# LB_BIT_w9_PROTO-v03_3_3.net
KiCad netlist of a schematic drawn in EAGLE
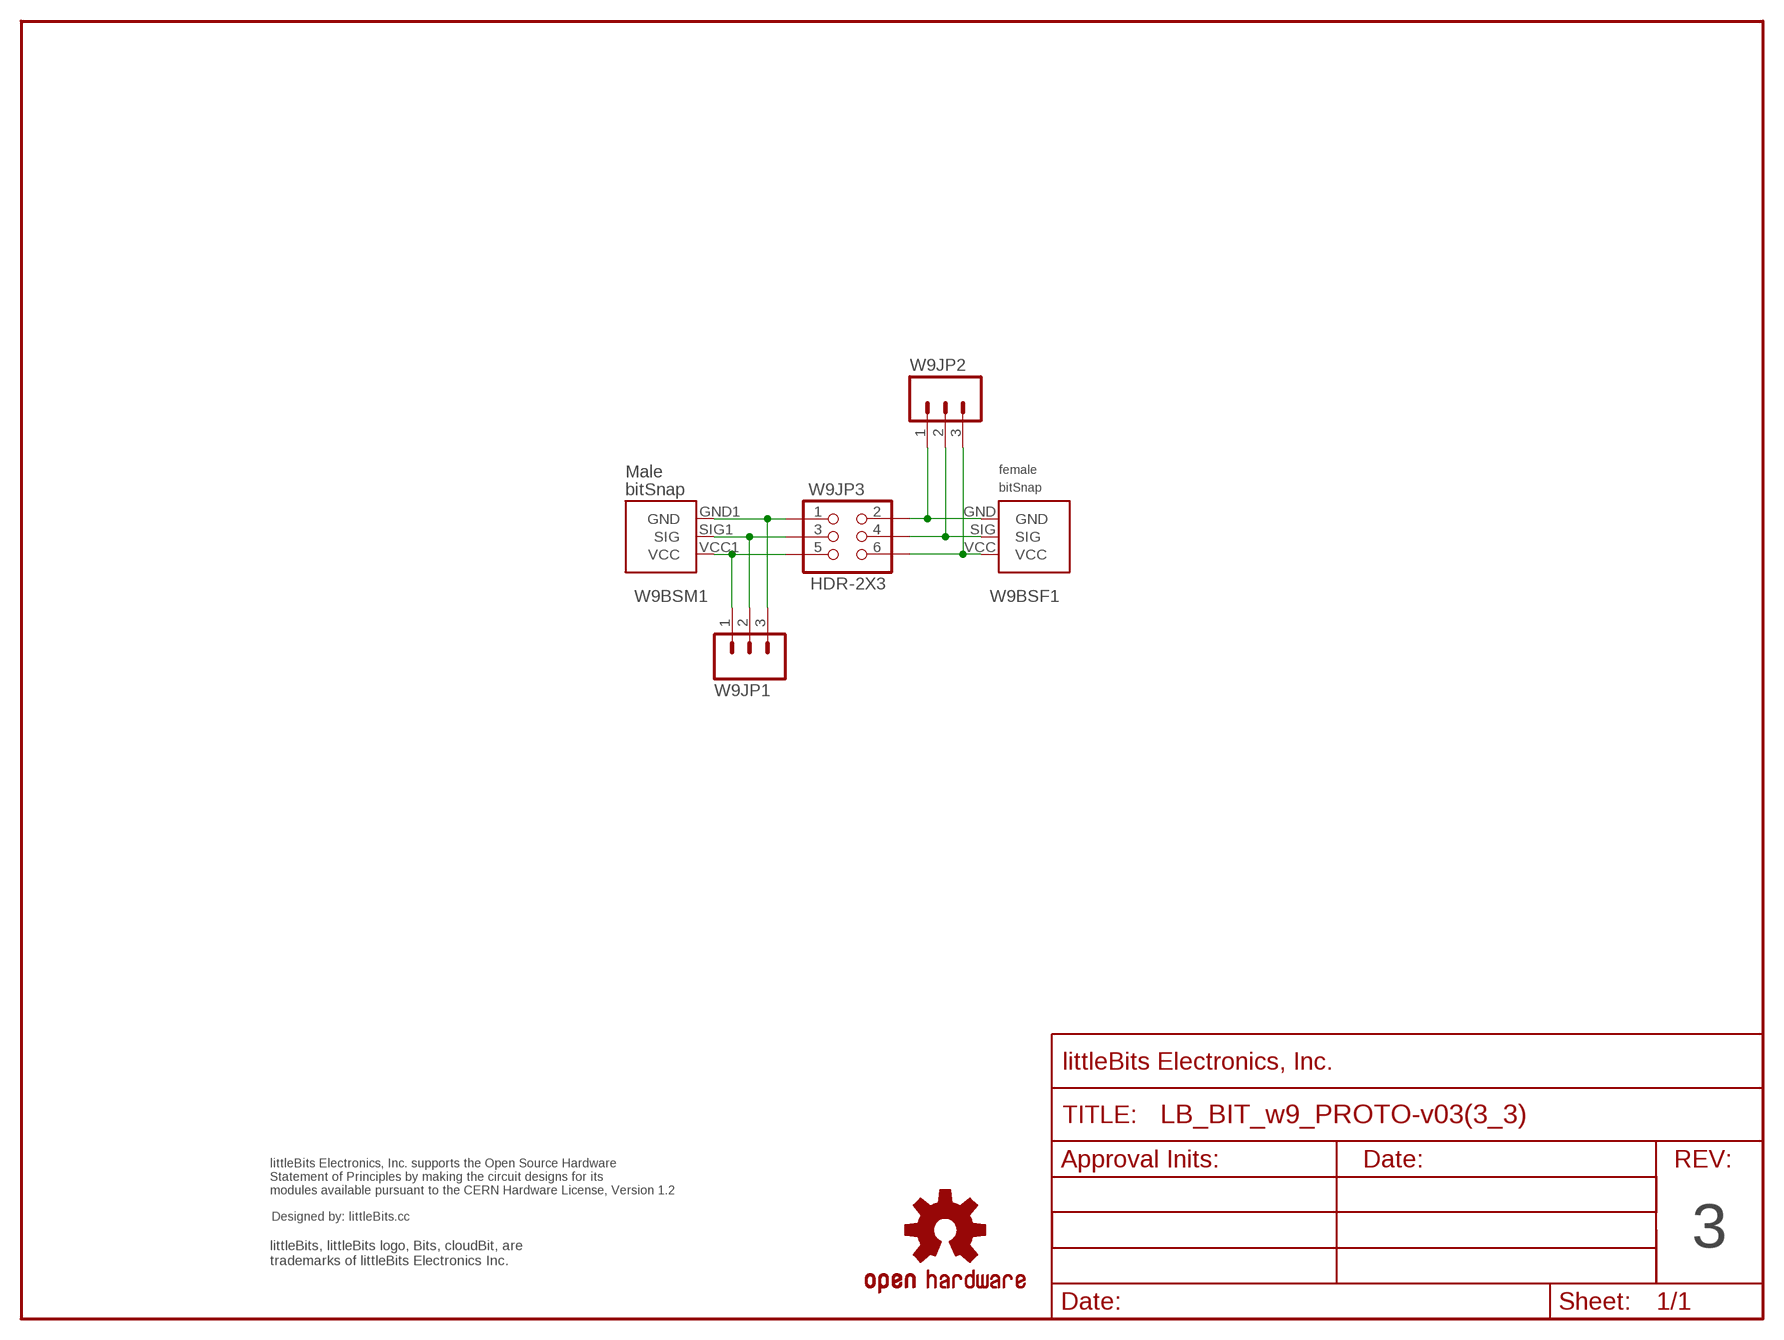
[diagram p0: schematic, sheet 1]

(export (version "E")
  (design (tool "Eeschema 10.0.6"))
  (components
    (comp (ref "U$5")
      (value "OSHWCREDIT")
      (footprint "eagle-import:OSHWCREDIT")
      (libsource (lib "eagle-import") (part "OSHWCREDIT"))
    )
    (comp (ref "U$11")
      (value "OSHW-LOGOL")
      (footprint "eagle-import:OSHW-LOGO-L")
      (libsource (lib "eagle-import") (part "OSHW-LOGOL"))
    )
    (comp (ref "U$13")
      (value "FRAME-LETTER-OHWOHW")
      (footprint "eagle-import:FABDWG01-OHW")
      (libsource (lib "eagle-import") (part "FRAME-LETTER-OHWOHW"))
    )
    (comp (ref "W9BSF1")
      (value "BITSNAP_V03_FEMALE\"")
      (footprint "eagle-import:BITSNAP_V03_FEMALE_NO_ARROW")
      (libsource (lib "eagle-import") (part "BITSNAP_V03_FEMALE{dblquote}"))
    )
    (comp (ref "W9BSM1")
      (value "BITSNAP_V03_MALE")
      (footprint "eagle-import:BITSNAP_V03_MALE")
      (libsource (lib "eagle-import") (part "BITSNAP_V03_MALE"))
    )
    (comp (ref "W9JP1")
      (value "SCREW-TERMINAL-3PIN-2.54MM")
      (footprint "eagle-import:22-23-2031")
      (libsource (lib "eagle-import") (part "SCREW-TERMINAL-3PIN-2.54MM"))
    )
    (comp (ref "W9JP2")
      (value "SCREW-TERMINAL-3PIN-2.54MM")
      (footprint "eagle-import:22-23-2031")
      (libsource (lib "eagle-import") (part "SCREW-TERMINAL-3PIN-2.54MM"))
    )
    (comp (ref "W9JP3")
      (value "HDR-2X3")
      (footprint "eagle-import:2X03")
      (libsource (lib "eagle-import") (part "HDR-2X3"))
    )
  )
  (nets
    (net (code "1") (name "Net-(W9BSF1-PadGND)") (class "Default")
      (node (ref "W9BSF1") (pin "GND") (pinfunction "GND_GND") (pintype "bidirectional"))
      (node (ref "W9JP2") (pin "1") (pinfunction "1_1") (pintype "passive"))
      (node (ref "W9JP3") (pin "2") (pinfunction "2_2") (pintype "passive"))
    )
    (net (code "2") (name "Net-(W9BSF1-PadSIG)") (class "Default")
      (node (ref "W9BSF1") (pin "SIG") (pinfunction "SIG_SIG") (pintype "bidirectional"))
      (node (ref "W9JP2") (pin "2") (pinfunction "2_2") (pintype "passive"))
      (node (ref "W9JP3") (pin "4") (pinfunction "4_4") (pintype "passive"))
    )
    (net (code "3") (name "Net-(W9BSF1-PadVCC)") (class "Default")
      (node (ref "W9BSF1") (pin "VCC") (pinfunction "VCC_VCC") (pintype "bidirectional"))
      (node (ref "W9JP2") (pin "3") (pinfunction "3_3") (pintype "passive"))
      (node (ref "W9JP3") (pin "6") (pinfunction "6_6") (pintype "passive"))
    )
    (net (code "4") (name "Net-(W9BSM1-GND)") (class "Default")
      (node (ref "W9BSM1") (pin "GND1") (pinfunction "GND_GND1") (pintype "bidirectional"))
      (node (ref "W9JP1") (pin "3") (pinfunction "3_3") (pintype "passive"))
      (node (ref "W9JP3") (pin "1") (pinfunction "1_1") (pintype "passive"))
    )
    (net (code "5") (name "Net-(W9BSM1-SIG)") (class "Default")
      (node (ref "W9BSM1") (pin "SIG1") (pinfunction "SIG_SIG1") (pintype "bidirectional"))
      (node (ref "W9JP1") (pin "2") (pinfunction "2_2") (pintype "passive"))
      (node (ref "W9JP3") (pin "3") (pinfunction "3_3") (pintype "passive"))
    )
    (net (code "6") (name "Net-(W9BSM1-VCC)") (class "Default")
      (node (ref "W9BSM1") (pin "VCC1") (pinfunction "VCC_VCC1") (pintype "bidirectional"))
      (node (ref "W9JP1") (pin "1") (pinfunction "1_1") (pintype "passive"))
      (node (ref "W9JP3") (pin "5") (pinfunction "5_5") (pintype "passive"))
    )
  )
)
